# Manchester_c.net
KiCad netlist of a schematic drawn in EAGLE
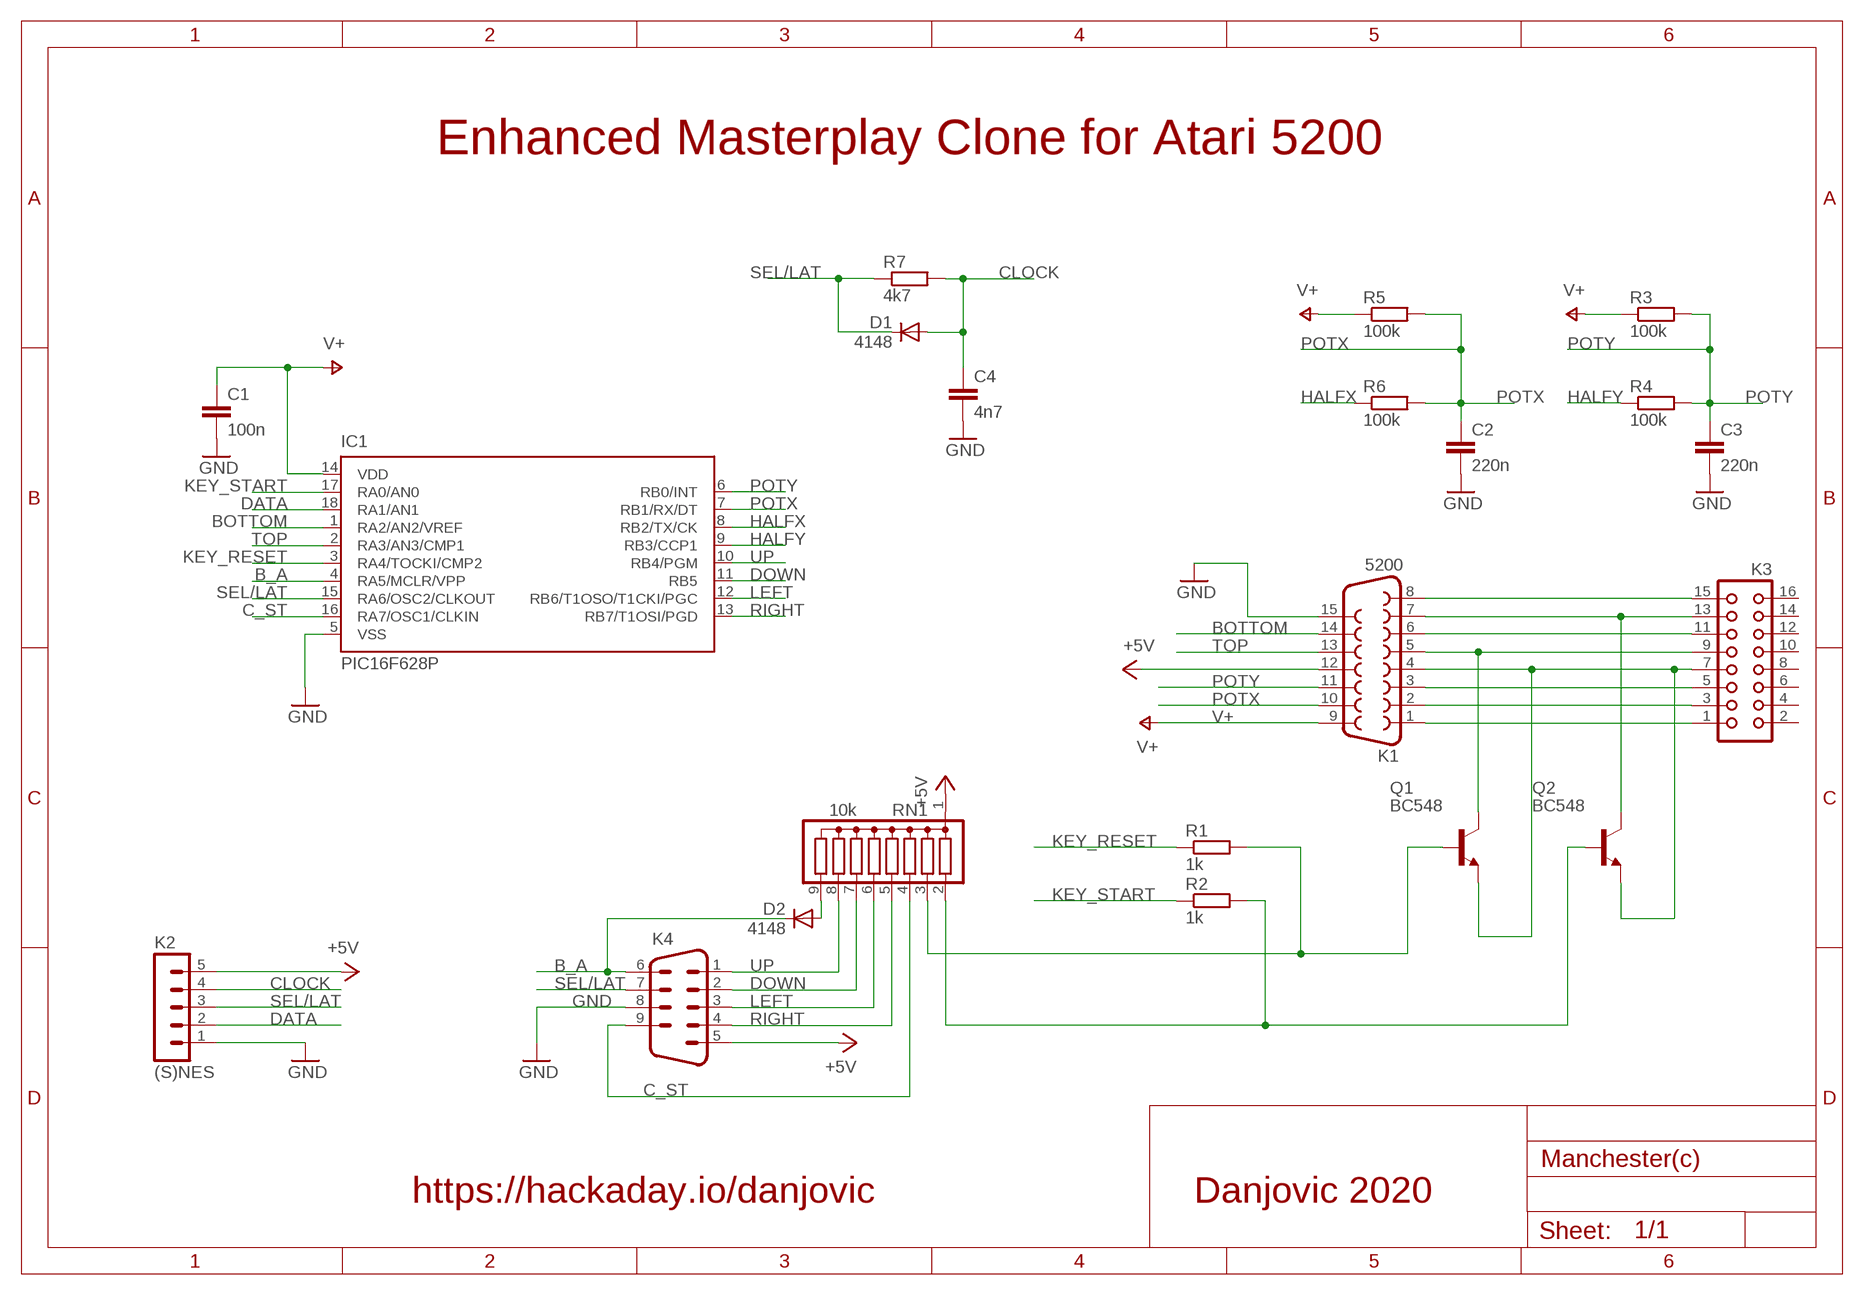
[diagram p0: schematic, sheet 1]

(export (version "E")
  (design (tool "Eeschema 10.0.6"))
  (components
    (comp (ref "C1")
      (value "100n")
      (footprint "eagle-import:C050-024X044")
      (libsource (lib "eagle-import") (part "C-EU050-024X044"))
    )
    (comp (ref "C2")
      (value "220n")
      (footprint "eagle-import:C050-024X044")
      (libsource (lib "eagle-import") (part "C-EU050-024X044"))
    )
    (comp (ref "C3")
      (value "220n")
      (footprint "eagle-import:C050-024X044")
      (libsource (lib "eagle-import") (part "C-EU050-024X044"))
    )
    (comp (ref "C4")
      (value "4n7")
      (footprint "eagle-import:C050-024X044")
      (libsource (lib "eagle-import") (part "C-EU050-024X044"))
    )
    (comp (ref "D1")
      (value "4148")
      (footprint "eagle-import:D-5")
      (libsource (lib "eagle-import") (part "DIODE-D-5"))
    )
    (comp (ref "D2")
      (value "4148")
      (footprint "eagle-import:D-5")
      (libsource (lib "eagle-import") (part "DIODE-D-5"))
    )
    (comp (ref "IC1")
      (value "PIC16F628P")
      (footprint "eagle-import:DIL18")
      (fields (field (name "MF") "MICROCHIP") (field (name "MPN") "PIC16F628-04I/P"))
      (libsource (lib "eagle-import") (part "PIC16F62P8"))
    )
    (comp (ref "K1")
      (value "5200")
      (footprint "eagle-import:F15D")
      (libsource (lib "eagle-import") (part "F15D"))
    )
    (comp (ref "K2")
      (value "(S)NES")
      (footprint "eagle-import:MA05-1")
      (libsource (lib "eagle-import") (part "MA05-1"))
    )
    (comp (ref "K3")
      (value "CON16L")
      (footprint "eagle-import:CON16L")
      (libsource (lib "eagle-import") (part "CON16L"))
    )
    (comp (ref "K4")
      (value "M09D")
      (footprint "eagle-import:M09D")
      (libsource (lib "eagle-import") (part "M09D"))
    )
    (comp (ref "Q1")
      (value "BC548")
      (footprint "eagle-import:TO92")
      (libsource (lib "eagle-import") (part "BC548"))
    )
    (comp (ref "Q2")
      (value "BC548")
      (footprint "eagle-import:TO92")
      (libsource (lib "eagle-import") (part "BC548"))
    )
    (comp (ref "R1")
      (value "1k")
      (footprint "eagle-import:0204_7")
      (libsource (lib "eagle-import") (part "R-EU_0204/7"))
    )
    (comp (ref "R2")
      (value "1k")
      (footprint "eagle-import:0204_7")
      (libsource (lib "eagle-import") (part "R-EU_0204/7"))
    )
    (comp (ref "R3")
      (value "100k")
      (footprint "eagle-import:0204_7")
      (libsource (lib "eagle-import") (part "R-EU_0204/7"))
    )
    (comp (ref "R4")
      (value "100k")
      (footprint "eagle-import:0204_7")
      (libsource (lib "eagle-import") (part "R-EU_0204/7"))
    )
    (comp (ref "R5")
      (value "100k")
      (footprint "eagle-import:0204_7")
      (libsource (lib "eagle-import") (part "R-EU_0204/7"))
    )
    (comp (ref "R6")
      (value "100k")
      (footprint "eagle-import:0204_7")
      (libsource (lib "eagle-import") (part "R-EU_0204/7"))
    )
    (comp (ref "R7")
      (value "4k7")
      (footprint "eagle-import:0204_7")
      (libsource (lib "eagle-import") (part "R-EU_0204/7"))
    )
    (comp (ref "RN1")
      (value "10k")
      (footprint "eagle-import:SIL9")
      (libsource (lib "eagle-import") (part "G08R"))
    )
  )
  (nets
    (net (code "1") (name "+5V") (class "Default")
      (node (ref "K1") (pin "12") (pinfunction "12_12") (pintype "passive"))
      (node (ref "K2") (pin "5") (pinfunction "5_5") (pintype "passive"))
      (node (ref "K4") (pin "5") (pinfunction "5_5") (pintype "passive"))
      (node (ref "RN1") (pin "1") (pinfunction "1_1") (pintype "passive"))
    )
    (net (code "2") (name "/BOTTOM") (class "Default")
      (node (ref "IC1") (pin "1") (pinfunction "RA2/AN2/VREF_1") (pintype "bidirectional"))
      (node (ref "K1") (pin "14") (pinfunction "14_14") (pintype "passive"))
    )
    (net (code "3") (name "/B_A") (class "Default")
      (node (ref "D2") (pin "C") (pinfunction "C_C") (pintype "passive"))
      (node (ref "IC1") (pin "4") (pinfunction "RA5/MCLR/VPP_4") (pintype "bidirectional"))
      (node (ref "K4") (pin "6") (pinfunction "6_6") (pintype "passive"))
    )
    (net (code "4") (name "/CLOCK") (class "Default")
      (node (ref "C4") (pin "1") (pinfunction "1_1") (pintype "passive"))
      (node (ref "D1") (pin "A") (pinfunction "A_A") (pintype "passive"))
      (node (ref "K2") (pin "4") (pinfunction "4_4") (pintype "passive"))
      (node (ref "R7") (pin "2") (pinfunction "2_2") (pintype "passive"))
    )
    (net (code "5") (name "/C_ST") (class "Default")
      (node (ref "IC1") (pin "16") (pinfunction "RA7/OSC1/CLKIN_16") (pintype "bidirectional"))
      (node (ref "K4") (pin "9") (pinfunction "9_9") (pintype "passive"))
      (node (ref "RN1") (pin "4") (pinfunction "4_4") (pintype "passive"))
    )
    (net (code "6") (name "/DATA") (class "Default")
      (node (ref "IC1") (pin "18") (pinfunction "RA1/AN1_18") (pintype "bidirectional"))
      (node (ref "K2") (pin "2") (pinfunction "2_2") (pintype "passive"))
    )
    (net (code "7") (name "/DOWN") (class "Default")
      (node (ref "IC1") (pin "11") (pinfunction "RB5_11") (pintype "bidirectional"))
      (node (ref "K4") (pin "2") (pinfunction "2_2") (pintype "passive"))
      (node (ref "RN1") (pin "7") (pinfunction "7_7") (pintype "passive"))
    )
    (net (code "8") (name "/HALFX") (class "Default")
      (node (ref "IC1") (pin "8") (pinfunction "RB2/TX/CK_8") (pintype "bidirectional"))
      (node (ref "R6") (pin "1") (pinfunction "1_1") (pintype "passive"))
    )
    (net (code "9") (name "/HALFY") (class "Default")
      (node (ref "IC1") (pin "9") (pinfunction "RB3/CCP1_9") (pintype "bidirectional"))
      (node (ref "R4") (pin "1") (pinfunction "1_1") (pintype "passive"))
    )
    (net (code "10") (name "/KEY_RESET") (class "Default")
      (node (ref "IC1") (pin "3") (pinfunction "RA4/TOCKI/CMP2_3") (pintype "bidirectional"))
      (node (ref "R1") (pin "1") (pinfunction "1_1") (pintype "passive"))
    )
    (net (code "11") (name "/KEY_START") (class "Default")
      (node (ref "IC1") (pin "17") (pinfunction "RA0/AN0_17") (pintype "bidirectional"))
      (node (ref "R2") (pin "1") (pinfunction "1_1") (pintype "passive"))
    )
    (net (code "12") (name "/LEFT") (class "Default")
      (node (ref "IC1") (pin "12") (pinfunction "RB6/T1OSO/T1CKI/PGC_12") (pintype "bidirectional"))
      (node (ref "K4") (pin "3") (pinfunction "3_3") (pintype "passive"))
      (node (ref "RN1") (pin "6") (pinfunction "6_6") (pintype "passive"))
    )
    (net (code "13") (name "/POTX") (class "Default")
      (node (ref "C2") (pin "1") (pinfunction "1_1") (pintype "passive"))
      (node (ref "IC1") (pin "7") (pinfunction "RB1/RX/DT_7") (pintype "bidirectional"))
      (node (ref "K1") (pin "10") (pinfunction "10_10") (pintype "passive"))
      (node (ref "R5") (pin "2") (pinfunction "2_2") (pintype "passive"))
      (node (ref "R6") (pin "2") (pinfunction "2_2") (pintype "passive"))
    )
    (net (code "14") (name "/POTY") (class "Default")
      (node (ref "C3") (pin "1") (pinfunction "1_1") (pintype "passive"))
      (node (ref "IC1") (pin "6") (pinfunction "RB0/INT_6") (pintype "bidirectional"))
      (node (ref "K1") (pin "11") (pinfunction "11_11") (pintype "passive"))
      (node (ref "R3") (pin "2") (pinfunction "2_2") (pintype "passive"))
      (node (ref "R4") (pin "2") (pinfunction "2_2") (pintype "passive"))
    )
    (net (code "15") (name "/RIGHT") (class "Default")
      (node (ref "IC1") (pin "13") (pinfunction "RB7/T1OSI/PGD_13") (pintype "bidirectional"))
      (node (ref "K4") (pin "4") (pinfunction "4_4") (pintype "passive"))
      (node (ref "RN1") (pin "5") (pinfunction "5_5") (pintype "passive"))
    )
    (net (code "16") (name "/SEL{slash}LAT") (class "Default")
      (node (ref "D1") (pin "C") (pinfunction "C_C") (pintype "passive"))
      (node (ref "IC1") (pin "15") (pinfunction "RA6/OSC2/CLKOUT_15") (pintype "bidirectional"))
      (node (ref "K2") (pin "3") (pinfunction "3_3") (pintype "passive"))
      (node (ref "K4") (pin "7") (pinfunction "7_7") (pintype "passive"))
      (node (ref "R7") (pin "1") (pinfunction "1_1") (pintype "passive"))
    )
    (net (code "17") (name "/TOP") (class "Default")
      (node (ref "IC1") (pin "2") (pinfunction "RA3/AN3/CMP1_2") (pintype "bidirectional"))
      (node (ref "K1") (pin "13") (pinfunction "13_13") (pintype "passive"))
    )
    (net (code "18") (name "/UP") (class "Default")
      (node (ref "IC1") (pin "10") (pinfunction "RB4/PGM_10") (pintype "bidirectional"))
      (node (ref "K4") (pin "1") (pinfunction "1_1") (pintype "passive"))
      (node (ref "RN1") (pin "8") (pinfunction "8_8") (pintype "passive"))
    )
    (net (code "19") (name "GND") (class "Default")
      (node (ref "C1") (pin "2") (pinfunction "2_2") (pintype "passive"))
      (node (ref "C2") (pin "2") (pinfunction "2_2") (pintype "passive"))
      (node (ref "C3") (pin "2") (pinfunction "2_2") (pintype "passive"))
      (node (ref "C4") (pin "2") (pinfunction "2_2") (pintype "passive"))
      (node (ref "IC1") (pin "5") (pinfunction "VSS_5") (pintype "power_in"))
      (node (ref "K1") (pin "15") (pinfunction "15_15") (pintype "passive"))
      (node (ref "K2") (pin "1") (pinfunction "1_1") (pintype "passive"))
      (node (ref "K4") (pin "8") (pinfunction "8_8") (pintype "passive"))
    )
    (net (code "20") (name "Net-(D2-PadA)") (class "Default")
      (node (ref "D2") (pin "A") (pinfunction "A_A") (pintype "passive"))
      (node (ref "RN1") (pin "9") (pinfunction "9_9") (pintype "passive"))
    )
    (net (code "21") (name "Net-(K1-Pad1)") (class "Default")
      (node (ref "K1") (pin "1") (pinfunction "1_1") (pintype "passive"))
      (node (ref "K3") (pin "1") (pinfunction "1_1") (pintype "passive"))
    )
    (net (code "22") (name "Net-(K1-Pad2)") (class "Default")
      (node (ref "K1") (pin "2") (pinfunction "2_2") (pintype "passive"))
      (node (ref "K3") (pin "3") (pinfunction "3_3") (pintype "passive"))
    )
    (net (code "23") (name "Net-(K1-Pad3)") (class "Default")
      (node (ref "K1") (pin "3") (pinfunction "3_3") (pintype "passive"))
      (node (ref "K3") (pin "5") (pinfunction "5_5") (pintype "passive"))
    )
    (net (code "24") (name "Net-(K1-Pad6)") (class "Default")
      (node (ref "K1") (pin "6") (pinfunction "6_6") (pintype "passive"))
      (node (ref "K3") (pin "11") (pinfunction "11_11") (pintype "passive"))
    )
    (net (code "25") (name "Net-(K1-Pad8)") (class "Default")
      (node (ref "K1") (pin "8") (pinfunction "8_8") (pintype "passive"))
      (node (ref "K3") (pin "15") (pinfunction "15_15") (pintype "passive"))
    )
    (net (code "26") (name "Net-(Q1-B)") (class "Default")
      (node (ref "Q1") (pin "2") (pinfunction "B_2") (pintype "passive"))
      (node (ref "R1") (pin "2") (pinfunction "2_2") (pintype "passive"))
      (node (ref "RN1") (pin "3") (pinfunction "3_3") (pintype "passive"))
    )
    (net (code "27") (name "Net-(Q1-C)") (class "Default")
      (node (ref "K1") (pin "5") (pinfunction "5_5") (pintype "passive"))
      (node (ref "K3") (pin "9") (pinfunction "9_9") (pintype "passive"))
      (node (ref "Q1") (pin "3") (pinfunction "C_3") (pintype "passive"))
    )
    (net (code "28") (name "Net-(Q1-E)") (class "Default")
      (node (ref "K1") (pin "4") (pinfunction "4_4") (pintype "passive"))
      (node (ref "K3") (pin "7") (pinfunction "7_7") (pintype "passive"))
      (node (ref "Q1") (pin "1") (pinfunction "E_1") (pintype "passive"))
      (node (ref "Q2") (pin "1") (pinfunction "E_1") (pintype "passive"))
    )
    (net (code "29") (name "Net-(Q2-B)") (class "Default")
      (node (ref "Q2") (pin "2") (pinfunction "B_2") (pintype "passive"))
      (node (ref "R2") (pin "2") (pinfunction "2_2") (pintype "passive"))
      (node (ref "RN1") (pin "2") (pinfunction "2_2") (pintype "passive"))
    )
    (net (code "30") (name "Net-(Q2-C)") (class "Default")
      (node (ref "K1") (pin "7") (pinfunction "7_7") (pintype "passive"))
      (node (ref "K3") (pin "13") (pinfunction "13_13") (pintype "passive"))
      (node (ref "Q2") (pin "3") (pinfunction "C_3") (pintype "passive"))
    )
    (net (code "31") (name "V+") (class "Default")
      (node (ref "C1") (pin "1") (pinfunction "1_1") (pintype "passive"))
      (node (ref "IC1") (pin "14") (pinfunction "VDD_14") (pintype "power_in"))
      (node (ref "K1") (pin "9") (pinfunction "9_9") (pintype "passive"))
      (node (ref "R3") (pin "1") (pinfunction "1_1") (pintype "passive"))
      (node (ref "R5") (pin "1") (pinfunction "1_1") (pintype "passive"))
    )
    (net (code "32") (name "unconnected-(K3-Pad2)") (class "Default")
      (node (ref "K3") (pin "2") (pinfunction "2_2") (pintype "passive"))
    )
    (net (code "33") (name "unconnected-(K3-Pad4)") (class "Default")
      (node (ref "K3") (pin "4") (pinfunction "4_4") (pintype "passive"))
    )
    (net (code "34") (name "unconnected-(K3-Pad6)") (class "Default")
      (node (ref "K3") (pin "6") (pinfunction "6_6") (pintype "passive"))
    )
    (net (code "35") (name "unconnected-(K3-Pad8)") (class "Default")
      (node (ref "K3") (pin "8") (pinfunction "8_8") (pintype "passive"))
    )
    (net (code "36") (name "unconnected-(K3-Pad10)") (class "Default")
      (node (ref "K3") (pin "10") (pinfunction "10_10") (pintype "passive"))
    )
    (net (code "37") (name "unconnected-(K3-Pad12)") (class "Default")
      (node (ref "K3") (pin "12") (pinfunction "12_12") (pintype "passive"))
    )
    (net (code "38") (name "unconnected-(K3-Pad14)") (class "Default")
      (node (ref "K3") (pin "14") (pinfunction "14_14") (pintype "passive"))
    )
    (net (code "39") (name "unconnected-(K3-Pad16)") (class "Default")
      (node (ref "K3") (pin "16") (pinfunction "16_16") (pintype "passive"))
    )
  )
)
